# Main.net
KiCad netlist of a schematic drawn in Altium Designer
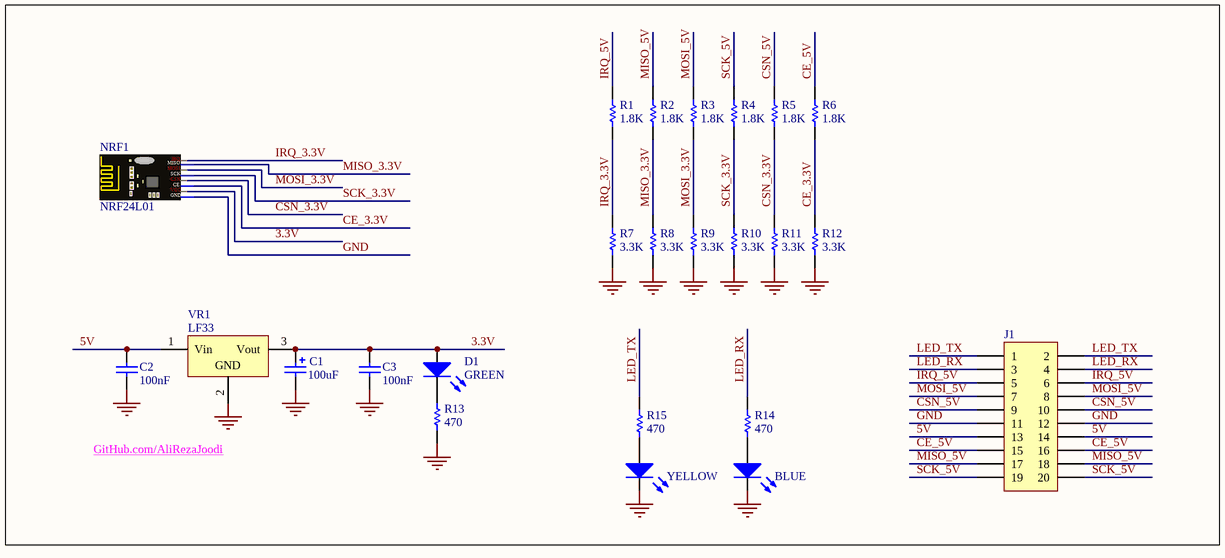
[diagram p0: Main.SchDoc]

(export (version "E")
  (design (tool "Eeschema 10.0.6"))
  (components
    (comp (ref "C1")
      (value "100uF")
      (footprint "CAPPR2.5-6.3x5")
      (description "Polarized Capacitor (Radial)")
      (fields (field (name "MANUFACTURER") "Generic Components") (field (name "PUBLISHER") "Altium Limited"))
      (libsource (lib "Miscellaneous Devices") (part "Cap Pol1"))
    )
    (comp (ref "C2")
      (value "100nF")
      (footprint "CAPNTO2.54-3.05x1.78A")
      (description "Capacitor")
      (fields (field (name "MANUFACTURER") "Generic Components") (field (name "PUBLISHER") "Altium Limited"))
      (libsource (lib "Miscellaneous Devices") (part "Cap"))
    )
    (comp (ref "C3")
      (value "100nF")
      (footprint "CAPNTO2.54-3.05x1.78A")
      (description "Capacitor")
      (fields (field (name "MANUFACTURER") "Generic Components") (field (name "PUBLISHER") "Altium Limited"))
      (libsource (lib "Miscellaneous Devices") (part "Cap"))
    )
    (comp (ref "D1")
      (value "GREEN")
      (footprint "LED-5mm_Red")
      (description "Typical INFRARED GaAs LED")
      (fields (field (name "MANUFACTURER") "Generic Components") (field (name "PUBLISHER") "Altium Limited"))
      (libsource (lib "Miscellaneous Devices") (part "LED"))
    )
    (comp (ref "D2")
      (value "BLUE")
      (footprint "LED-5mm_Red")
      (description "Typical INFRARED GaAs LED")
      (fields (field (name "MANUFACTURER") "Generic Components") (field (name "PUBLISHER") "Altium Limited"))
      (libsource (lib "Miscellaneous Devices") (part "LED"))
    )
    (comp (ref "D3")
      (value "YELLOW")
      (footprint "LED-5mm_Red")
      (description "Typical INFRARED GaAs LED")
      (fields (field (name "MANUFACTURER") "Generic Components") (field (name "PUBLISHER") "Altium Limited"))
      (libsource (lib "Miscellaneous Devices") (part "LED"))
    )
    (comp (ref "J1")
      (value "Header 10X2")
      (footprint "FKV20SN")
      (description "Header, 10-Pin, Dual row")
      (fields (field (name "MANUFACTURER") "Generic Components") (field (name "PUBLISHER") "Altium Limited"))
      (libsource (lib "Miscellaneous Connectors") (part "Header 10X2"))
    )
    (comp (ref "NRF1")
      (value "NRF24L01")
      (footprint "NRF24L01+PA+LNA")
      (libsource (lib "NRF24L01") (part "NRF24L01"))
    )
    (comp (ref "R1")
      (value "1.8K")
      (footprint "AXIAL-0.4")
      (description "Resistor")
      (fields (field (name "PUBLISHER") "Altium Limited"))
      (libsource (lib "Miscellaneous Devices") (part "Res1"))
    )
    (comp (ref "R2")
      (value "1.8K")
      (footprint "AXIAL-0.4")
      (description "Resistor")
      (fields (field (name "PUBLISHER") "Altium Limited"))
      (libsource (lib "Miscellaneous Devices") (part "Res1"))
    )
    (comp (ref "R3")
      (value "1.8K")
      (footprint "AXIAL-0.4")
      (description "Resistor")
      (fields (field (name "PUBLISHER") "Altium Limited"))
      (libsource (lib "Miscellaneous Devices") (part "Res1"))
    )
    (comp (ref "R4")
      (value "1.8K")
      (footprint "AXIAL-0.4")
      (description "Resistor")
      (fields (field (name "PUBLISHER") "Altium Limited"))
      (libsource (lib "Miscellaneous Devices") (part "Res1"))
    )
    (comp (ref "R5")
      (value "1.8K")
      (footprint "AXIAL-0.4")
      (description "Resistor")
      (fields (field (name "PUBLISHER") "Altium Limited"))
      (libsource (lib "Miscellaneous Devices") (part "Res1"))
    )
    (comp (ref "R6")
      (value "1.8K")
      (footprint "AXIAL-0.4")
      (description "Resistor")
      (fields (field (name "PUBLISHER") "Altium Limited"))
      (libsource (lib "Miscellaneous Devices") (part "Res1"))
    )
    (comp (ref "R7")
      (value "3.3K")
      (footprint "AXIAL-0.4")
      (description "Resistor")
      (fields (field (name "PUBLISHER") "Altium Limited"))
      (libsource (lib "Miscellaneous Devices") (part "Res1"))
    )
    (comp (ref "R8")
      (value "3.3K")
      (footprint "AXIAL-0.4")
      (description "Resistor")
      (fields (field (name "PUBLISHER") "Altium Limited"))
      (libsource (lib "Miscellaneous Devices") (part "Res1"))
    )
    (comp (ref "R9")
      (value "3.3K")
      (footprint "AXIAL-0.4")
      (description "Resistor")
      (fields (field (name "PUBLISHER") "Altium Limited"))
      (libsource (lib "Miscellaneous Devices") (part "Res1"))
    )
    (comp (ref "R10")
      (value "3.3K")
      (footprint "AXIAL-0.4")
      (description "Resistor")
      (fields (field (name "PUBLISHER") "Altium Limited"))
      (libsource (lib "Miscellaneous Devices") (part "Res1"))
    )
    (comp (ref "R11")
      (value "3.3K")
      (footprint "AXIAL-0.4")
      (description "Resistor")
      (fields (field (name "PUBLISHER") "Altium Limited"))
      (libsource (lib "Miscellaneous Devices") (part "Res1"))
    )
    (comp (ref "R12")
      (value "3.3K")
      (footprint "AXIAL-0.4")
      (description "Resistor")
      (fields (field (name "PUBLISHER") "Altium Limited"))
      (libsource (lib "Miscellaneous Devices") (part "Res1"))
    )
    (comp (ref "R13")
      (value "470")
      (footprint "AXIAL-0.4")
      (description "Resistor")
      (fields (field (name "PUBLISHER") "Altium Limited"))
      (libsource (lib "Miscellaneous Devices") (part "Res1"))
    )
    (comp (ref "R14")
      (value "470")
      (footprint "AXIAL-0.4")
      (description "Resistor")
      (fields (field (name "PUBLISHER") "Altium Limited"))
      (libsource (lib "Miscellaneous Devices") (part "Res1"))
    )
    (comp (ref "R15")
      (value "470")
      (footprint "AXIAL-0.4")
      (description "Resistor")
      (fields (field (name "PUBLISHER") "Altium Limited"))
      (libsource (lib "Miscellaneous Devices") (part "Res1"))
    )
    (comp (ref "VR1")
      (value "LF33")
      (footprint "TO257H_2")
      (description "Voltage Regulator")
      (fields (field (name "MANUFACTURER") "Generic Components") (field (name "PUBLISHER") "Altium Limited"))
      (libsource (lib "my Libraries") (part "Volt Reg"))
    )
  )
  (nets
    (net (code "1") (name "/3.3V") (class "Default")
      (node (ref "C1") (pin "1") (pinfunction "1_1") (pintype "passive"))
      (node (ref "C3") (pin "2") (pinfunction "2_2") (pintype "passive"))
      (node (ref "D1") (pin "1") (pinfunction "A_1") (pintype "passive"))
      (node (ref "NRF1") (pin "VCC") (pinfunction "VCC_VCC") (pintype "power_in"))
      (node (ref "VR1") (pin "3") (pinfunction "Vout_3") (pintype "passive"))
    )
    (net (code "2") (name "/5V") (class "Default")
      (node (ref "C2") (pin "2") (pinfunction "2_2") (pintype "passive"))
      (node (ref "J1") (pin "13") (pinfunction "13_13") (pintype "passive"))
      (node (ref "J1") (pin "14") (pinfunction "14_14") (pintype "passive"))
      (node (ref "VR1") (pin "1") (pinfunction "Vin_1") (pintype "passive"))
    )
    (net (code "3") (name "/CE_3.3V") (class "Default")
      (node (ref "NRF1") (pin "CE") (pinfunction "CE_CE") (pintype "passive"))
      (node (ref "R12") (pin "1") (pinfunction "1_1") (pintype "passive"))
      (node (ref "R6") (pin "2") (pinfunction "2_2") (pintype "passive"))
    )
    (net (code "4") (name "/CE_5V") (class "Default")
      (node (ref "J1") (pin "15") (pinfunction "15_15") (pintype "passive"))
      (node (ref "J1") (pin "16") (pinfunction "16_16") (pintype "passive"))
      (node (ref "R6") (pin "1") (pinfunction "1_1") (pintype "passive"))
    )
    (net (code "5") (name "/CSN_3.3V") (class "Default")
      (node (ref "NRF1") (pin "CSN") (pinfunction "CSN_CSN") (pintype "passive"))
      (node (ref "R11") (pin "1") (pinfunction "1_1") (pintype "passive"))
      (node (ref "R5") (pin "2") (pinfunction "2_2") (pintype "passive"))
    )
    (net (code "6") (name "/CSN_5V") (class "Default")
      (node (ref "J1") (pin "10") (pinfunction "10_10") (pintype "passive"))
      (node (ref "J1") (pin "9") (pinfunction "9_9") (pintype "passive"))
      (node (ref "R5") (pin "1") (pinfunction "1_1") (pintype "passive"))
    )
    (net (code "7") (name "/IRQ_3.3V") (class "Default")
      (node (ref "NRF1") (pin "IRQ") (pinfunction "IRQ_IRQ") (pintype "passive"))
      (node (ref "R1") (pin "2") (pinfunction "2_2") (pintype "passive"))
      (node (ref "R7") (pin "1") (pinfunction "1_1") (pintype "passive"))
    )
    (net (code "8") (name "/IRQ_5V") (class "Default")
      (node (ref "J1") (pin "5") (pinfunction "5_5") (pintype "passive"))
      (node (ref "J1") (pin "6") (pinfunction "6_6") (pintype "passive"))
      (node (ref "R1") (pin "1") (pinfunction "1_1") (pintype "passive"))
    )
    (net (code "9") (name "/LED_RX") (class "Default")
      (node (ref "J1") (pin "3") (pinfunction "3_3") (pintype "passive"))
      (node (ref "J1") (pin "4") (pinfunction "4_4") (pintype "passive"))
      (node (ref "R14") (pin "1") (pinfunction "1_1") (pintype "passive"))
    )
    (net (code "10") (name "/LED_TX") (class "Default")
      (node (ref "J1") (pin "1") (pinfunction "1_1") (pintype "passive"))
      (node (ref "J1") (pin "2") (pinfunction "2_2") (pintype "passive"))
      (node (ref "R15") (pin "1") (pinfunction "1_1") (pintype "passive"))
    )
    (net (code "11") (name "/MISO_3.3V") (class "Default")
      (node (ref "NRF1") (pin "MISO") (pinfunction "MISO_MISO") (pintype "passive"))
      (node (ref "R2") (pin "2") (pinfunction "2_2") (pintype "passive"))
      (node (ref "R8") (pin "1") (pinfunction "1_1") (pintype "passive"))
    )
    (net (code "12") (name "/MISO_5V") (class "Default")
      (node (ref "J1") (pin "17") (pinfunction "17_17") (pintype "passive"))
      (node (ref "J1") (pin "18") (pinfunction "18_18") (pintype "passive"))
      (node (ref "R2") (pin "1") (pinfunction "1_1") (pintype "passive"))
    )
    (net (code "13") (name "/MOSI_3.3V") (class "Default")
      (node (ref "NRF1") (pin "MOSI") (pinfunction "MOSI_MOSI") (pintype "passive"))
      (node (ref "R3") (pin "2") (pinfunction "2_2") (pintype "passive"))
      (node (ref "R9") (pin "1") (pinfunction "1_1") (pintype "passive"))
    )
    (net (code "14") (name "/MOSI_5V") (class "Default")
      (node (ref "J1") (pin "7") (pinfunction "7_7") (pintype "passive"))
      (node (ref "J1") (pin "8") (pinfunction "8_8") (pintype "passive"))
      (node (ref "R3") (pin "1") (pinfunction "1_1") (pintype "passive"))
    )
    (net (code "15") (name "/SCK_3.3V") (class "Default")
      (node (ref "NRF1") (pin "SCK") (pinfunction "SCK_SCK") (pintype "passive"))
      (node (ref "R10") (pin "1") (pinfunction "1_1") (pintype "passive"))
      (node (ref "R4") (pin "2") (pinfunction "2_2") (pintype "passive"))
    )
    (net (code "16") (name "/SCK_5V") (class "Default")
      (node (ref "J1") (pin "19") (pinfunction "19_19") (pintype "passive"))
      (node (ref "J1") (pin "20") (pinfunction "20_20") (pintype "passive"))
      (node (ref "R4") (pin "1") (pinfunction "1_1") (pintype "passive"))
    )
    (net (code "17") (name "GND") (class "Default")
      (node (ref "C1") (pin "2") (pinfunction "2_2") (pintype "passive"))
      (node (ref "C2") (pin "1") (pinfunction "1_1") (pintype "passive"))
      (node (ref "C3") (pin "1") (pinfunction "1_1") (pintype "passive"))
      (node (ref "D2") (pin "2") (pinfunction "K_2") (pintype "passive"))
      (node (ref "D3") (pin "2") (pinfunction "K_2") (pintype "passive"))
      (node (ref "J1") (pin "11") (pinfunction "11_11") (pintype "passive"))
      (node (ref "J1") (pin "12") (pinfunction "12_12") (pintype "passive"))
      (node (ref "NRF1") (pin "GND") (pinfunction "GND_GND") (pintype "power_in"))
      (node (ref "R10") (pin "2") (pinfunction "2_2") (pintype "passive"))
      (node (ref "R11") (pin "2") (pinfunction "2_2") (pintype "passive"))
      (node (ref "R12") (pin "2") (pinfunction "2_2") (pintype "passive"))
      (node (ref "R13") (pin "2") (pinfunction "2_2") (pintype "passive"))
      (node (ref "R7") (pin "2") (pinfunction "2_2") (pintype "passive"))
      (node (ref "R8") (pin "2") (pinfunction "2_2") (pintype "passive"))
      (node (ref "R9") (pin "2") (pinfunction "2_2") (pintype "passive"))
      (node (ref "VR1") (pin "2") (pinfunction "GND_2") (pintype "passive"))
    )
    (net (code "18") (name "Net-(D1-K)") (class "Default")
      (node (ref "D1") (pin "2") (pinfunction "K_2") (pintype "passive"))
      (node (ref "R13") (pin "1") (pinfunction "1_1") (pintype "passive"))
    )
    (net (code "19") (name "Net-(D2-A)") (class "Default")
      (node (ref "D2") (pin "1") (pinfunction "A_1") (pintype "passive"))
      (node (ref "R14") (pin "2") (pinfunction "2_2") (pintype "passive"))
    )
    (net (code "20") (name "Net-(D3-A)") (class "Default")
      (node (ref "D3") (pin "1") (pinfunction "A_1") (pintype "passive"))
      (node (ref "R15") (pin "2") (pinfunction "2_2") (pintype "passive"))
    )
  )
)
